# 2020-03-08_LN2_Autofill_Controller.net
KiCad netlist of a schematic drawn in EAGLE
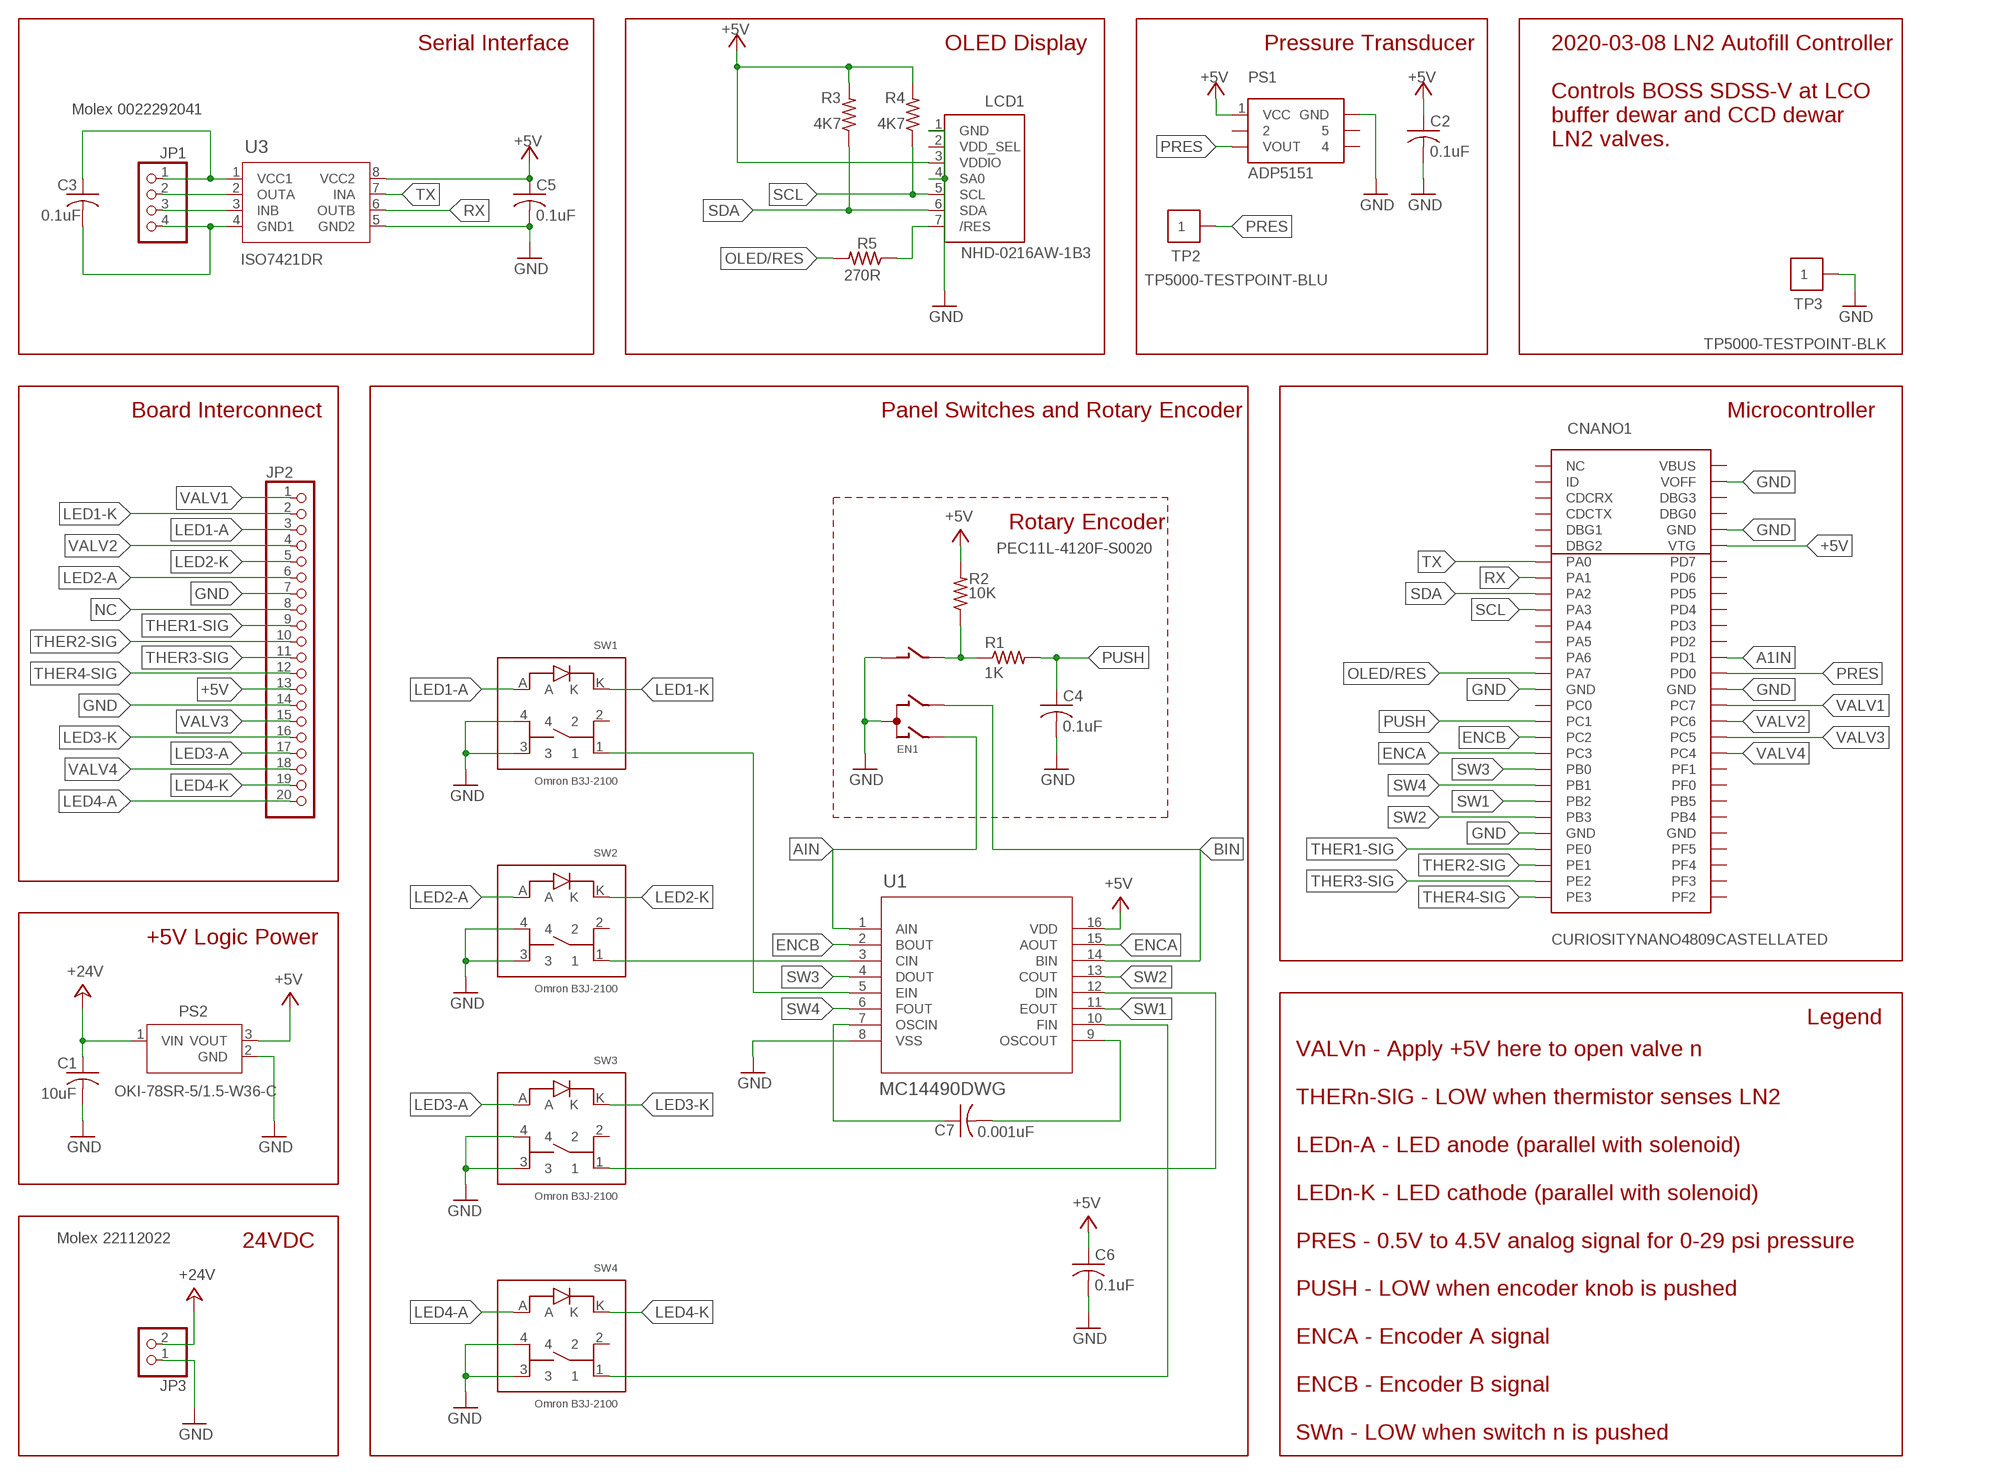
[diagram p0: schematic, sheet 1]

(export (version "E")
  (design (tool "Eeschema 10.0.6"))
  (components
    (comp (ref "C1")
      (value "10uF")
      (footprint "eagle-import:C1210K")
      (libsource (lib "eagle-import") (part "C-USC1210K"))
    )
    (comp (ref "C2")
      (value "0.1uF")
      (footprint "eagle-import:C0805")
      (libsource (lib "eagle-import") (part "C-USC0805"))
    )
    (comp (ref "C3")
      (value "0.1uF")
      (footprint "eagle-import:C0805")
      (libsource (lib "eagle-import") (part "C-USC0805"))
    )
    (comp (ref "C4")
      (value "0.1uF")
      (footprint "eagle-import:C0805")
      (libsource (lib "eagle-import") (part "C-USC0805"))
    )
    (comp (ref "C5")
      (value "0.1uF")
      (footprint "eagle-import:C0805")
      (libsource (lib "eagle-import") (part "C-USC0805"))
    )
    (comp (ref "C6")
      (value "0.1uF")
      (footprint "eagle-import:C0805")
      (libsource (lib "eagle-import") (part "C-USC0805"))
    )
    (comp (ref "C7")
      (value "0.001uF")
      (footprint "eagle-import:C0805")
      (libsource (lib "eagle-import") (part "C-USC0805"))
    )
    (comp (ref "CNANO1")
      (value "CURIOSITYNANO4809CASTELLATED")
      (footprint "eagle-import:CURIOSITYNANO4809CASTELLATED")
      (libsource (lib "eagle-import") (part "CURIOSITYNANO4809CASTELLATED"))
    )
    (comp (ref "EN1")
      (value "PEC11L-4120F-S0020")
      (footprint "eagle-import:ENC-BOURNES-PEC11L")
      (libsource (lib "eagle-import") (part "ENC-BOURNES-PEC11L"))
    )
    (comp (ref "JP1")
      (value "Molex 0022292041")
      (footprint "eagle-import:MOLEX-04-VERT")
      (libsource (lib "eagle-import") (part "PINHD-1X4MOLEX-04-VERT"))
    )
    (comp (ref "JP2")
      (value "PINHD-1X20")
      (footprint "eagle-import:1X20")
      (libsource (lib "eagle-import") (part "PINHD-1X20"))
    )
    (comp (ref "JP3")
      (value "Molex 22112022")
      (footprint "eagle-import:MOLEX-02-VERT")
      (libsource (lib "eagle-import") (part "PINHD-1X2MOLEX-02-VERT"))
    )
    (comp (ref "LCD1")
      (value "NHD-0216AW-1B3")
      (footprint "eagle-import:LCD-NEWHAVEN-16X2")
      (libsource (lib "eagle-import") (part "LCD-NEWHAVEN-16X2"))
    )
    (comp (ref "PS1")
      (value "ADP5151")
      (footprint "eagle-import:PRESSURE-SENSOR-ADP5151")
      (libsource (lib "eagle-import") (part "PRESSURE-SENSOR-ADP5151"))
    )
    (comp (ref "PS2")
      (value "OKI-78SR-5/1.5-W36-C")
      (footprint "eagle-import:CONV_OKI-78SR-5_1.5-W36-C")
      (fields
        (field (name "DIGI-KEY_PART_NUMBER") "811-2196-5-ND")
        (field (name "MF") "Murata Power Solutions Inc.")
      )
      (libsource (lib "eagle-import") (part "OKI-78SR-5/1.5-W36-C"))
    )
    (comp (ref "R1")
      (value "1K")
      (footprint "eagle-import:R0805")
      (libsource (lib "eagle-import") (part "R-US_R0805"))
    )
    (comp (ref "R2")
      (value "10K")
      (footprint "eagle-import:R0805")
      (libsource (lib "eagle-import") (part "R-US_R0805"))
    )
    (comp (ref "R3")
      (value "4K7")
      (footprint "eagle-import:R0805")
      (libsource (lib "eagle-import") (part "R-US_R0805"))
    )
    (comp (ref "R4")
      (value "4K7")
      (footprint "eagle-import:R0805")
      (libsource (lib "eagle-import") (part "R-US_R0805"))
    )
    (comp (ref "R5")
      (value "270R")
      (footprint "eagle-import:R0805")
      (libsource (lib "eagle-import") (part "R-US_R0805"))
    )
    (comp (ref "SW1")
      (value "Omron B3J-2100")
      (footprint "eagle-import:SWITCH-OMRON-B3J-1LED")
      (libsource (lib "eagle-import") (part "SWITCH-OMRON-B3J-1LED"))
    )
    (comp (ref "SW2")
      (value "Omron B3J-2100")
      (footprint "eagle-import:SWITCH-OMRON-B3J-1LED")
      (libsource (lib "eagle-import") (part "SWITCH-OMRON-B3J-1LED"))
    )
    (comp (ref "SW3")
      (value "Omron B3J-2100")
      (footprint "eagle-import:SWITCH-OMRON-B3J-1LED")
      (libsource (lib "eagle-import") (part "SWITCH-OMRON-B3J-1LED"))
    )
    (comp (ref "SW4")
      (value "Omron B3J-2100")
      (footprint "eagle-import:SWITCH-OMRON-B3J-1LED")
      (libsource (lib "eagle-import") (part "SWITCH-OMRON-B3J-1LED"))
    )
    (comp (ref "TP2")
      (value "TP5000-TESTPOINT-BLU")
      (footprint "eagle-import:TP5000-TESTPOINT-BLU")
      (libsource (lib "eagle-import") (part "TP5000-TESTPOINT-BLU"))
    )
    (comp (ref "TP3")
      (value "TP5000-TESTPOINT-BLK")
      (footprint "eagle-import:TP5000-TESTPOINT-BLK")
      (libsource (lib "eagle-import") (part "TP5000-TESTPOINT-BLK"))
    )
    (comp (ref "U1")
      (value "MC14490DWG")
      (footprint "eagle-import:SOIC127P1030X265-16N")
      (libsource (lib "eagle-import") (part "DEBOUNCER-MC14490DWGSOIC-16-WB"))
    )
    (comp (ref "U3")
      (value "ISO7421DR")
      (footprint "eagle-import:SOIC127P599X175-8N")
      (libsource (lib "eagle-import") (part "ISO7421DRTI-SOIC-D8"))
    )
  )
  (nets
    (net (code "1") (name "+5V") (class "Default")
      (node (ref "C2") (pin "1") (pinfunction "1_1") (pintype "passive"))
      (node (ref "C5") (pin "1") (pinfunction "1_1") (pintype "passive"))
      (node (ref "C6") (pin "1") (pinfunction "1_1") (pintype "passive"))
      (node (ref "CNANO1") (pin "VTG") (pinfunction "VTG_VTG") (pintype "bidirectional"))
      (node (ref "JP2") (pin "13") (pinfunction "13_13") (pintype "passive"))
      (node (ref "LCD1") (pin "3") (pinfunction "VDDIO_3") (pintype "bidirectional"))
      (node (ref "PS1") (pin "1") (pinfunction "VCC_1") (pintype "bidirectional"))
      (node (ref "PS2") (pin "3") (pinfunction "VOUT_3") (pintype "power_in"))
      (node (ref "R2") (pin "2") (pinfunction "2_2") (pintype "passive"))
      (node (ref "R3") (pin "2") (pinfunction "2_2") (pintype "passive"))
      (node (ref "R4") (pin "2") (pinfunction "2_2") (pintype "passive"))
      (node (ref "U1") (pin "16") (pinfunction "VDD_16") (pintype "power_in"))
      (node (ref "U3") (pin "8") (pinfunction "VCC2_8") (pintype "power_in"))
    )
    (net (code "2") (name "+24V") (class "Default")
      (node (ref "C1") (pin "1") (pinfunction "1_1") (pintype "passive"))
      (node (ref "JP3") (pin "2") (pinfunction "2_2") (pintype "passive"))
      (node (ref "PS2") (pin "1") (pinfunction "VIN_1") (pintype "input"))
    )
    (net (code "3") (name "A1IN") (class "Default")
      (node (ref "CNANO1") (pin "PD1-AIN1") (pinfunction "PD1_PD1-AIN1") (pintype "bidirectional"))
    )
    (net (code "4") (name "AIN") (class "Default")
      (node (ref "EN1") (pin "A") (pinfunction "A_A") (pintype "passive"))
      (node (ref "U1") (pin "1") (pinfunction "AIN_1") (pintype "input"))
    )
    (net (code "5") (name "BIN") (class "Default")
      (node (ref "EN1") (pin "B") (pinfunction "B_B") (pintype "passive"))
      (node (ref "U1") (pin "14") (pinfunction "BIN_14") (pintype "input"))
    )
    (net (code "6") (name "ENCA") (class "Default")
      (node (ref "CNANO1") (pin "PC3") (pinfunction "PC3_PC3") (pintype "bidirectional"))
      (node (ref "U1") (pin "15") (pinfunction "AOUT_15") (pintype "output"))
    )
    (net (code "7") (name "ENCB") (class "Default")
      (node (ref "CNANO1") (pin "PC2") (pinfunction "PC2_PC2") (pintype "bidirectional"))
      (node (ref "U1") (pin "2") (pinfunction "BOUT_2") (pintype "output"))
    )
    (net (code "8") (name "GND") (class "Default")
      (node (ref "C1") (pin "2") (pinfunction "2_2") (pintype "passive"))
      (node (ref "C2") (pin "2") (pinfunction "2_2") (pintype "passive"))
      (node (ref "C4") (pin "2") (pinfunction "2_2") (pintype "passive"))
      (node (ref "C5") (pin "2") (pinfunction "2_2") (pintype "passive"))
      (node (ref "C6") (pin "2") (pinfunction "2_2") (pintype "passive"))
      (node (ref "CNANO1") (pin "GND15") (pinfunction "GND_GND15") (pintype "bidirectional"))
      (node (ref "CNANO1") (pin "GND24") (pinfunction "GND_GND24") (pintype "bidirectional"))
      (node (ref "CNANO1") (pin "GND42") (pinfunction "GND_GND42") (pintype "bidirectional"))
      (node (ref "CNANO1") (pin "GND52") (pinfunction "GND_GND52") (pintype "bidirectional"))
      (node (ref "CNANO1") (pin "VOFF") (pinfunction "VOFF_VOFF") (pintype "bidirectional"))
      (node (ref "EN1") (pin "2") (pinfunction "C1_2") (pintype "passive"))
      (node (ref "EN1") (pin "C") (pinfunction "C_C") (pintype "passive"))
      (node (ref "JP2") (pin "14") (pinfunction "14_14") (pintype "passive"))
      (node (ref "JP2") (pin "7") (pinfunction "7_7") (pintype "passive"))
      (node (ref "JP3") (pin "1") (pinfunction "1_1") (pintype "passive"))
      (node (ref "LCD1") (pin "1") (pinfunction "GND_1") (pintype "bidirectional"))
      (node (ref "LCD1") (pin "4") (pinfunction "SA0_4") (pintype "bidirectional"))
      (node (ref "PS1") (pin "6") (pinfunction "GND_6") (pintype "bidirectional"))
      (node (ref "PS2") (pin "2") (pinfunction "GND_2") (pintype "power_in"))
      (node (ref "SW1") (pin "3") (pinfunction "3_3") (pintype "bidirectional"))
      (node (ref "SW1") (pin "4") (pinfunction "4_4") (pintype "bidirectional"))
      (node (ref "SW2") (pin "3") (pinfunction "3_3") (pintype "bidirectional"))
      (node (ref "SW2") (pin "4") (pinfunction "4_4") (pintype "bidirectional"))
      (node (ref "SW3") (pin "3") (pinfunction "3_3") (pintype "bidirectional"))
      (node (ref "SW3") (pin "4") (pinfunction "4_4") (pintype "bidirectional"))
      (node (ref "SW4") (pin "3") (pinfunction "3_3") (pintype "bidirectional"))
      (node (ref "SW4") (pin "4") (pinfunction "4_4") (pintype "bidirectional"))
      (node (ref "TP3") (pin "P$1") (pinfunction "1_P$1") (pintype "bidirectional"))
      (node (ref "U1") (pin "8") (pinfunction "VSS_8") (pintype "power_in"))
      (node (ref "U3") (pin "5") (pinfunction "GND2_5") (pintype "power_in"))
    )
    (net (code "9") (name "LED1-A") (class "Default")
      (node (ref "JP2") (pin "3") (pinfunction "3_3") (pintype "passive"))
      (node (ref "SW1") (pin "A") (pinfunction "A_A") (pintype "bidirectional"))
    )
    (net (code "10") (name "LED1-K") (class "Default")
      (node (ref "JP2") (pin "2") (pinfunction "2_2") (pintype "passive"))
      (node (ref "SW1") (pin "K") (pinfunction "K_K") (pintype "bidirectional"))
    )
    (net (code "11") (name "LED2-A") (class "Default")
      (node (ref "JP2") (pin "6") (pinfunction "6_6") (pintype "passive"))
      (node (ref "SW2") (pin "A") (pinfunction "A_A") (pintype "bidirectional"))
    )
    (net (code "12") (name "LED2-K") (class "Default")
      (node (ref "JP2") (pin "5") (pinfunction "5_5") (pintype "passive"))
      (node (ref "SW2") (pin "K") (pinfunction "K_K") (pintype "bidirectional"))
    )
    (net (code "13") (name "LED3-A") (class "Default")
      (node (ref "JP2") (pin "17") (pinfunction "17_17") (pintype "passive"))
      (node (ref "SW3") (pin "A") (pinfunction "A_A") (pintype "bidirectional"))
    )
    (net (code "14") (name "LED3-K") (class "Default")
      (node (ref "JP2") (pin "16") (pinfunction "16_16") (pintype "passive"))
      (node (ref "SW3") (pin "K") (pinfunction "K_K") (pintype "bidirectional"))
    )
    (net (code "15") (name "LED4-A") (class "Default")
      (node (ref "JP2") (pin "20") (pinfunction "20_20") (pintype "passive"))
      (node (ref "SW4") (pin "A") (pinfunction "A_A") (pintype "bidirectional"))
    )
    (net (code "16") (name "LED4-K") (class "Default")
      (node (ref "JP2") (pin "19") (pinfunction "19_19") (pintype "passive"))
      (node (ref "SW4") (pin "K") (pinfunction "K_K") (pintype "bidirectional"))
    )
    (net (code "17") (name "NC") (class "Default")
      (node (ref "JP2") (pin "8") (pinfunction "8_8") (pintype "passive"))
    )
    (net (code "18") (name "Net-(EN1-B1)") (class "Default")
      (node (ref "EN1") (pin "1") (pinfunction "B1_1") (pintype "passive"))
      (node (ref "R1") (pin "1") (pinfunction "1_1") (pintype "passive"))
      (node (ref "R2") (pin "1") (pinfunction "1_1") (pintype "passive"))
    )
    (net (code "19") (name "Net-(LCD1-{slash}RES)") (class "Default")
      (node (ref "LCD1") (pin "7") (pinfunction "/RES_7") (pintype "bidirectional"))
      (node (ref "R5") (pin "1") (pinfunction "1_1") (pintype "passive"))
    )
    (net (code "20") (name "Net-(U1-CIN)") (class "Default")
      (node (ref "SW2") (pin "1") (pinfunction "1_1") (pintype "bidirectional"))
      (node (ref "U1") (pin "3") (pinfunction "CIN_3") (pintype "input"))
    )
    (net (code "21") (name "Net-(U1-DIN)") (class "Default")
      (node (ref "SW3") (pin "1") (pinfunction "1_1") (pintype "bidirectional"))
      (node (ref "U1") (pin "12") (pinfunction "DIN_12") (pintype "input"))
    )
    (net (code "22") (name "Net-(U1-EIN)") (class "Default")
      (node (ref "SW1") (pin "1") (pinfunction "1_1") (pintype "bidirectional"))
      (node (ref "U1") (pin "5") (pinfunction "EIN_5") (pintype "input"))
    )
    (net (code "23") (name "Net-(U1-FIN)") (class "Default")
      (node (ref "SW4") (pin "1") (pinfunction "1_1") (pintype "bidirectional"))
      (node (ref "U1") (pin "10") (pinfunction "FIN_10") (pintype "input"))
    )
    (net (code "24") (name "Net-(U1-OSCIN)") (class "Default")
      (node (ref "C7") (pin "1") (pinfunction "1_1") (pintype "passive"))
      (node (ref "U1") (pin "7") (pinfunction "OSCIN_7") (pintype "input"))
    )
    (net (code "25") (name "Net-(U1-OSCOUT)") (class "Default")
      (node (ref "C7") (pin "2") (pinfunction "2_2") (pintype "passive"))
      (node (ref "U1") (pin "9") (pinfunction "OSCOUT_9") (pintype "output"))
    )
    (net (code "26") (name "Net-(U3-GND1)") (class "Default")
      (node (ref "C3") (pin "2") (pinfunction "2_2") (pintype "passive"))
      (node (ref "JP1") (pin "4") (pinfunction "4_4") (pintype "passive"))
      (node (ref "U3") (pin "4") (pinfunction "GND1_4") (pintype "power_in"))
    )
    (net (code "27") (name "Net-(U3-INB)") (class "Default")
      (node (ref "JP1") (pin "3") (pinfunction "3_3") (pintype "passive"))
      (node (ref "U3") (pin "3") (pinfunction "INB_3") (pintype "input"))
    )
    (net (code "28") (name "Net-(U3-OUTA)") (class "Default")
      (node (ref "JP1") (pin "2") (pinfunction "2_2") (pintype "passive"))
      (node (ref "U3") (pin "2") (pinfunction "OUTA_2") (pintype "output"))
    )
    (net (code "29") (name "Net-(U3-VCC1)") (class "Default")
      (node (ref "C3") (pin "1") (pinfunction "1_1") (pintype "passive"))
      (node (ref "JP1") (pin "1") (pinfunction "1_1") (pintype "passive"))
      (node (ref "U3") (pin "1") (pinfunction "VCC1_1") (pintype "power_in"))
    )
    (net (code "30") (name "OLED{slash}RES") (class "Default")
      (node (ref "CNANO1") (pin "PA7-SS") (pinfunction "PA7_PA7-SS") (pintype "bidirectional"))
      (node (ref "R5") (pin "2") (pinfunction "2_2") (pintype "passive"))
    )
    (net (code "31") (name "PRES") (class "Default")
      (node (ref "CNANO1") (pin "PD0-AIN0") (pinfunction "PD0_PD0-AIN0") (pintype "bidirectional"))
      (node (ref "PS1") (pin "3") (pinfunction "VOUT_3") (pintype "bidirectional"))
      (node (ref "TP2") (pin "P$1") (pinfunction "1_P$1") (pintype "bidirectional"))
    )
    (net (code "32") (name "PUSH") (class "Default")
      (node (ref "C4") (pin "1") (pinfunction "1_1") (pintype "passive"))
      (node (ref "CNANO1") (pin "PC1-RX") (pinfunction "PC1_PC1-RX") (pintype "bidirectional"))
      (node (ref "R1") (pin "2") (pinfunction "2_2") (pintype "passive"))
    )
    (net (code "33") (name "RX") (class "Default")
      (node (ref "CNANO1") (pin "PA1-RX") (pinfunction "PA1_PA1-RX") (pintype "bidirectional"))
      (node (ref "U3") (pin "6") (pinfunction "OUTB_6") (pintype "output"))
    )
    (net (code "34") (name "SCL") (class "Default")
      (node (ref "CNANO1") (pin "PA3-SCL") (pinfunction "PA3_PA3-SCL") (pintype "bidirectional"))
      (node (ref "LCD1") (pin "5") (pinfunction "SCL_5") (pintype "bidirectional"))
      (node (ref "R4") (pin "1") (pinfunction "1_1") (pintype "passive"))
    )
    (net (code "35") (name "SDA") (class "Default")
      (node (ref "CNANO1") (pin "PA2-SDA") (pinfunction "PA2_PA2-SDA") (pintype "bidirectional"))
      (node (ref "LCD1") (pin "6") (pinfunction "SDA_6") (pintype "bidirectional"))
      (node (ref "R3") (pin "1") (pinfunction "1_1") (pintype "passive"))
    )
    (net (code "36") (name "SW1") (class "Default")
      (node (ref "CNANO1") (pin "PB2") (pinfunction "PB2_PB2") (pintype "bidirectional"))
      (node (ref "U1") (pin "11") (pinfunction "EOUT_11") (pintype "output"))
    )
    (net (code "37") (name "SW2") (class "Default")
      (node (ref "CNANO1") (pin "PB3") (pinfunction "PB3_PB3") (pintype "bidirectional"))
      (node (ref "U1") (pin "13") (pinfunction "COUT_13") (pintype "output"))
    )
    (net (code "38") (name "SW3") (class "Default")
      (node (ref "CNANO1") (pin "PB0-TX") (pinfunction "PB0_PB0-TX") (pintype "bidirectional"))
      (node (ref "U1") (pin "4") (pinfunction "DOUT_4") (pintype "output"))
    )
    (net (code "39") (name "SW4") (class "Default")
      (node (ref "CNANO1") (pin "PB1-RX") (pinfunction "PB1_PB1-RX") (pintype "bidirectional"))
      (node (ref "U1") (pin "6") (pinfunction "FOUT_6") (pintype "output"))
    )
    (net (code "40") (name "THER1-SIG") (class "Default")
      (node (ref "CNANO1") (pin "PE0") (pinfunction "PE0_PE0") (pintype "bidirectional"))
      (node (ref "JP2") (pin "9") (pinfunction "9_9") (pintype "passive"))
    )
    (net (code "41") (name "THER2-SIG") (class "Default")
      (node (ref "CNANO1") (pin "PE1") (pinfunction "PE1_PE1") (pintype "bidirectional"))
      (node (ref "JP2") (pin "10") (pinfunction "10_10") (pintype "passive"))
    )
    (net (code "42") (name "THER3-SIG") (class "Default")
      (node (ref "CNANO1") (pin "PE2") (pinfunction "PE2_PE2") (pintype "bidirectional"))
      (node (ref "JP2") (pin "11") (pinfunction "11_11") (pintype "passive"))
    )
    (net (code "43") (name "THER4-SIG") (class "Default")
      (node (ref "CNANO1") (pin "PE3") (pinfunction "PE3_PE3") (pintype "bidirectional"))
      (node (ref "JP2") (pin "12") (pinfunction "12_12") (pintype "passive"))
    )
    (net (code "44") (name "TX") (class "Default")
      (node (ref "CNANO1") (pin "PA0-TX") (pinfunction "PA0_PA0-TX") (pintype "bidirectional"))
      (node (ref "U3") (pin "7") (pinfunction "INA_7") (pintype "input"))
    )
    (net (code "45") (name "VALV1") (class "Default")
      (node (ref "CNANO1") (pin "PC7") (pinfunction "PC7_PC7") (pintype "bidirectional"))
      (node (ref "JP2") (pin "1") (pinfunction "1_1") (pintype "passive"))
    )
    (net (code "46") (name "VALV2") (class "Default")
      (node (ref "CNANO1") (pin "PC6") (pinfunction "PC6_PC6") (pintype "bidirectional"))
      (node (ref "JP2") (pin "4") (pinfunction "4_4") (pintype "passive"))
    )
    (net (code "47") (name "VALV3") (class "Default")
      (node (ref "CNANO1") (pin "PC5") (pinfunction "PC5_PC5") (pintype "bidirectional"))
      (node (ref "JP2") (pin "15") (pinfunction "15_15") (pintype "passive"))
    )
    (net (code "48") (name "VALV4") (class "Default")
      (node (ref "CNANO1") (pin "PC4") (pinfunction "PC4_PC4") (pintype "bidirectional"))
      (node (ref "JP2") (pin "18") (pinfunction "18_18") (pintype "passive"))
    )
    (net (code "49") (name "unconnected-(CNANO1-CDCRX-PadPB0-RX)") (class "Default")
      (node (ref "CNANO1") (pin "PB0-RX") (pinfunction "CDCRX_PB0-RX") (pintype "bidirectional"))
    )
    (net (code "50") (name "unconnected-(CNANO1-CDCTX-PadPB1-TX)") (class "Default")
      (node (ref "CNANO1") (pin "PB1-TX") (pinfunction "CDCTX_PB1-TX") (pintype "bidirectional"))
    )
    (net (code "51") (name "unconnected-(CNANO1-DBG0-PadUPDI)") (class "Default")
      (node (ref "CNANO1") (pin "UPDI") (pinfunction "DBG0_UPDI") (pintype "bidirectional"))
    )
    (net (code "52") (name "unconnected-(CNANO1-DBG1-PadPF3-5)") (class "Default")
      (node (ref "CNANO1") (pin "PF3-5") (pinfunction "DBG1_PF3-5") (pintype "bidirectional"))
    )
    (net (code "53") (name "unconnected-(CNANO1-DBG2-PadPF2-6)") (class "Default")
      (node (ref "CNANO1") (pin "PF2-6") (pinfunction "DBG2_PF2-6") (pintype "bidirectional"))
    )
    (net (code "54") (name "unconnected-(CNANO1-DBG3-PadPF6-SW0)") (class "Default")
      (node (ref "CNANO1") (pin "PF6-SW0") (pinfunction "DBG3_PF6-SW0") (pintype "bidirectional"))
    )
    (net (code "55") (name "unconnected-(CNANO1-GND-PadGND33)") (class "Default")
      (node (ref "CNANO1") (pin "GND33") (pinfunction "GND_GND33") (pintype "bidirectional"))
    )
    (net (code "56") (name "unconnected-(CNANO1-PA4-PadPA4-MOSI)") (class "Default")
      (node (ref "CNANO1") (pin "PA4-MOSI") (pinfunction "PA4_PA4-MOSI") (pintype "bidirectional"))
    )
    (net (code "57") (name "unconnected-(CNANO1-PA5-PadPA5-MISO)") (class "Default")
      (node (ref "CNANO1") (pin "PA5-MISO") (pinfunction "PA5_PA5-MISO") (pintype "bidirectional"))
    )
    (net (code "58") (name "unconnected-(CNANO1-PA6-PadPA6-SCK)") (class "Default")
      (node (ref "CNANO1") (pin "PA6-SCK") (pinfunction "PA6_PA6-SCK") (pintype "bidirectional"))
    )
    (net (code "59") (name "unconnected-(CNANO1-PC0-PadPC0-TX)") (class "Default")
      (node (ref "CNANO1") (pin "PC0-TX") (pinfunction "PC0_PC0-TX") (pintype "bidirectional"))
    )
    (net (code "60") (name "unconnected-(CNANO1-PD2-PadPD2-AIN2)") (class "Default")
      (node (ref "CNANO1") (pin "PD2-AIN2") (pinfunction "PD2_PD2-AIN2") (pintype "bidirectional"))
    )
    (net (code "61") (name "unconnected-(CNANO1-PD3-PadPD3-AIN3)") (class "Default")
      (node (ref "CNANO1") (pin "PD3-AIN3") (pinfunction "PD3_PD3-AIN3") (pintype "bidirectional"))
    )
    (net (code "62") (name "unconnected-(CNANO1-PD4-PadPD4-AIN4)") (class "Default")
      (node (ref "CNANO1") (pin "PD4-AIN4") (pinfunction "PD4_PD4-AIN4") (pintype "bidirectional"))
    )
    (net (code "63") (name "unconnected-(CNANO1-PD5-PadPD5-AIN5)") (class "Default")
      (node (ref "CNANO1") (pin "PD5-AIN5") (pinfunction "PD5_PD5-AIN5") (pintype "bidirectional"))
    )
    (net (code "64") (name "unconnected-(CNANO1-PD6-PadPD6-AIN6)") (class "Default")
      (node (ref "CNANO1") (pin "PD6-AIN6") (pinfunction "PD6_PD6-AIN6") (pintype "bidirectional"))
    )
    (net (code "65") (name "unconnected-(CNANO1-PD7-PadPD7-AIN7)") (class "Default")
      (node (ref "CNANO1") (pin "PD7-AIN7") (pinfunction "PD7_PD7-AIN7") (pintype "bidirectional"))
    )
    (net (code "66") (name "unconnected-(CNANO1-PF0-PadPF0-TOSC1)") (class "Default")
      (node (ref "CNANO1") (pin "PF0-TOSC1") (pinfunction "PF0_PF0-TOSC1") (pintype "bidirectional"))
    )
    (net (code "67") (name "unconnected-(CNANO1-PF1-PadPF1-TOSC2)") (class "Default")
      (node (ref "CNANO1") (pin "PF1-TOSC2") (pinfunction "PF1_PF1-TOSC2") (pintype "bidirectional"))
    )
    (net (code "68") (name "unconnected-(CNANO1-PF5-PadPF5-LED)") (class "Default")
      (node (ref "CNANO1") (pin "PF5-LED") (pinfunction "PF5_PF5-LED") (pintype "bidirectional"))
    )
    (net (code "69") (name "unconnected-(CNANO1-PadID)") (class "Default")
      (node (ref "CNANO1") (pin "ID") (pinfunction "ID_ID") (pintype "bidirectional"))
    )
    (net (code "70") (name "unconnected-(CNANO1-PadNC)") (class "Default")
      (node (ref "CNANO1") (pin "NC") (pinfunction "NC_NC") (pintype "bidirectional"))
    )
    (net (code "71") (name "unconnected-(CNANO1-PadPB4)") (class "Default")
      (node (ref "CNANO1") (pin "PB4") (pinfunction "PB4_PB4") (pintype "bidirectional"))
    )
    (net (code "72") (name "unconnected-(CNANO1-PadPB5)") (class "Default")
      (node (ref "CNANO1") (pin "PB5") (pinfunction "PB5_PB5") (pintype "bidirectional"))
    )
    (net (code "73") (name "unconnected-(CNANO1-PadPF2)") (class "Default")
      (node (ref "CNANO1") (pin "PF2") (pinfunction "PF2_PF2") (pintype "bidirectional"))
    )
    (net (code "74") (name "unconnected-(CNANO1-PadPF3)") (class "Default")
      (node (ref "CNANO1") (pin "PF3") (pinfunction "PF3_PF3") (pintype "bidirectional"))
    )
    (net (code "75") (name "unconnected-(CNANO1-PadPF4)") (class "Default")
      (node (ref "CNANO1") (pin "PF4") (pinfunction "PF4_PF4") (pintype "bidirectional"))
    )
    (net (code "76") (name "unconnected-(CNANO1-PadVBUS)") (class "Default")
      (node (ref "CNANO1") (pin "VBUS") (pinfunction "VBUS_VBUS") (pintype "bidirectional"))
    )
    (net (code "77") (name "unconnected-(LCD1-VDD_SEL-Pad2)") (class "Default")
      (node (ref "LCD1") (pin "2") (pinfunction "VDD_SEL_2") (pintype "bidirectional"))
    )
    (net (code "78") (name "unconnected-(PS1-Pad2)") (class "Default")
      (node (ref "PS1") (pin "2") (pinfunction "2_2") (pintype "bidirectional"))
    )
    (net (code "79") (name "unconnected-(PS1-Pad4)") (class "Default")
      (node (ref "PS1") (pin "4") (pinfunction "4_4") (pintype "bidirectional"))
    )
    (net (code "80") (name "unconnected-(PS1-Pad5)") (class "Default")
      (node (ref "PS1") (pin "5") (pinfunction "5_5") (pintype "bidirectional"))
    )
    (net (code "81") (name "unconnected-(SW1-Pad2)") (class "Default")
      (node (ref "SW1") (pin "2") (pinfunction "2_2") (pintype "bidirectional"))
    )
    (net (code "82") (name "unconnected-(SW2-Pad2)") (class "Default")
      (node (ref "SW2") (pin "2") (pinfunction "2_2") (pintype "bidirectional"))
    )
    (net (code "83") (name "unconnected-(SW3-Pad2)") (class "Default")
      (node (ref "SW3") (pin "2") (pinfunction "2_2") (pintype "bidirectional"))
    )
    (net (code "84") (name "unconnected-(SW4-Pad2)") (class "Default")
      (node (ref "SW4") (pin "2") (pinfunction "2_2") (pintype "bidirectional"))
    )
  )
)
